# mount.net
KiCad netlist of a schematic drawn in EAGLE
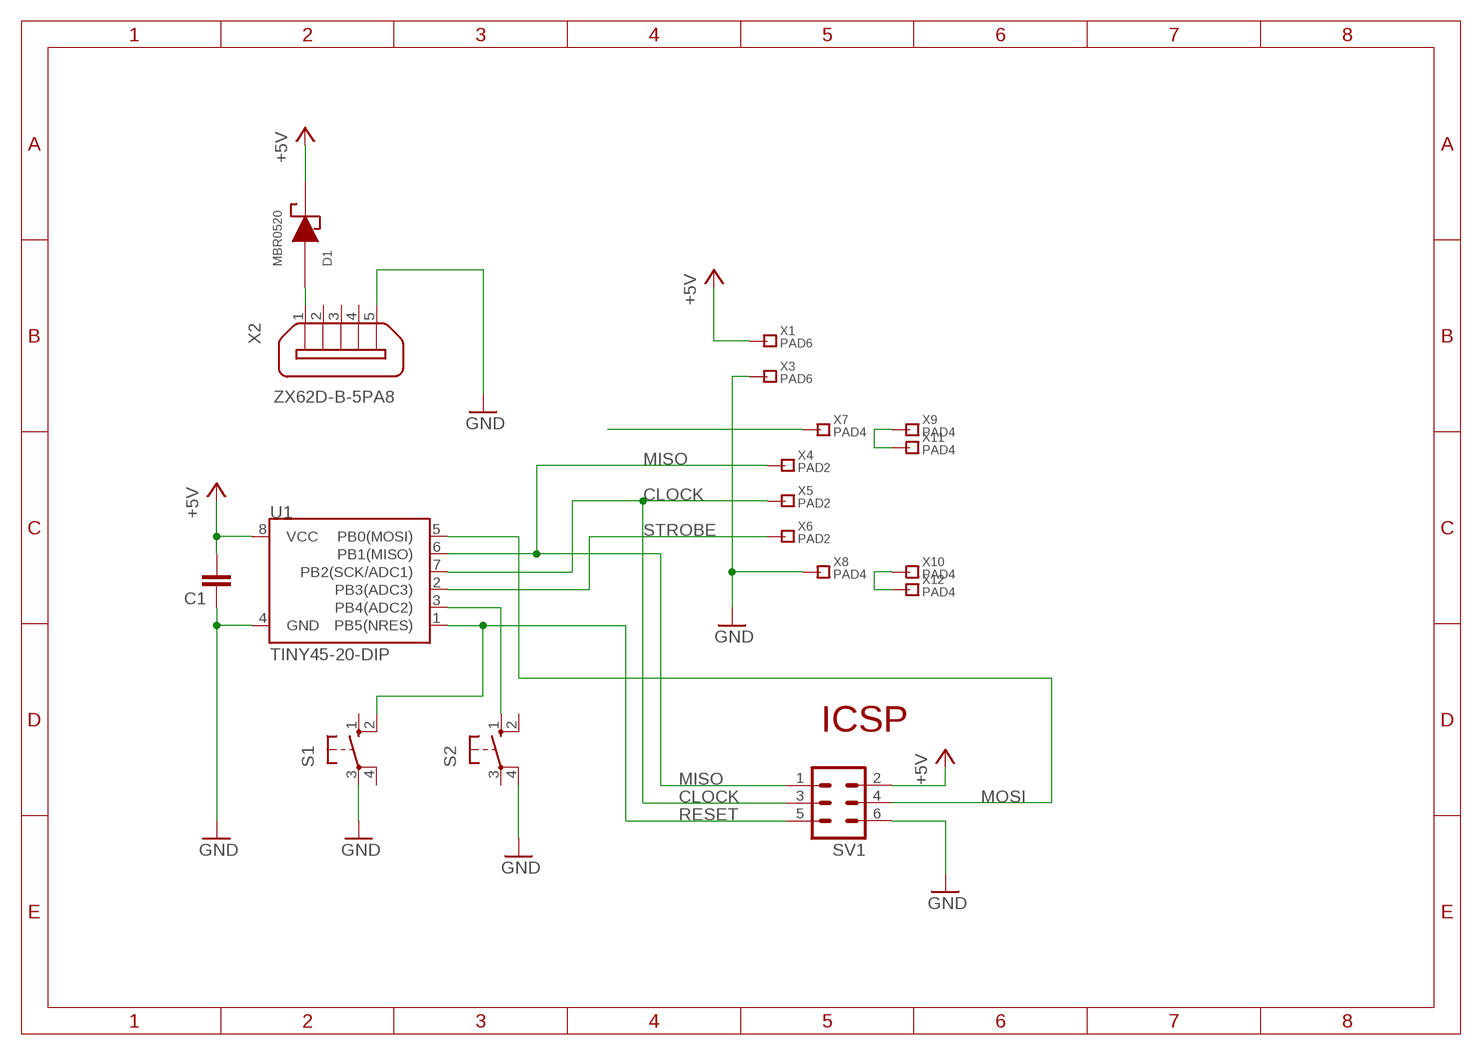
[diagram p0: schematic, sheet 1]

(export (version "E")
  (design (tool "Eeschema 10.0.6"))
  (components
    (comp (ref "C1")
      (value "C-EUC0805")
      (footprint "eagle-import:C0805")
      (libsource (lib "eagle-import") (part "C-EUC0805"))
    )
    (comp (ref "D1")
      (value "MBR0520")
      (footprint "eagle-import:SOD-123")
      (libsource (lib "eagle-import") (part "MBR0520"))
    )
    (comp (ref "S1")
      (value "10-XX")
      (footprint "eagle-import:B3F-10XX")
      (fields (field (name "MPN") "B3F-1000"))
      (libsource (lib "eagle-import") (part "10-XX"))
    )
    (comp (ref "S2")
      (value "10-XX")
      (footprint "eagle-import:B3F-10XX")
      (fields (field (name "MPN") "B3F-1000"))
      (libsource (lib "eagle-import") (part "10-XX"))
    )
    (comp (ref "SV1")
      (value "MA03-2")
      (footprint "eagle-import:MA03-2")
      (libsource (lib "eagle-import") (part "MA03-2"))
    )
    (comp (ref "U1")
      (value "TINY45-20-DIP")
      (footprint "eagle-import:DIP08_MCU")
      (libsource (lib "eagle-import") (part "ATTINY45TINY45-20-DIP"))
    )
    (comp (ref "X1")
      (value "PAD6")
      (footprint "eagle-import:SMDPAD")
      (libsource (lib "eagle-import") (part "PAD6"))
    )
    (comp (ref "X2")
      (value "ZX62D-B-5PA8")
      (footprint "eagle-import:ZX62D-B-5PA8")
      (fields (field (name "MF") "Hirose"))
      (libsource (lib "eagle-import") (part "ZX62D-B-5PA8"))
    )
    (comp (ref "X3")
      (value "PAD6")
      (footprint "eagle-import:SMDPAD")
      (libsource (lib "eagle-import") (part "PAD6"))
    )
    (comp (ref "X4")
      (value "PAD2")
      (footprint "eagle-import:SMDPAD_S")
      (libsource (lib "eagle-import") (part "PAD2"))
    )
    (comp (ref "X5")
      (value "PAD2")
      (footprint "eagle-import:SMDPAD_S")
      (libsource (lib "eagle-import") (part "PAD2"))
    )
    (comp (ref "X6")
      (value "PAD2")
      (footprint "eagle-import:SMDPAD_S")
      (libsource (lib "eagle-import") (part "PAD2"))
    )
    (comp (ref "X7")
      (value "PAD4")
      (footprint "eagle-import:SMDPAD_M")
      (libsource (lib "eagle-import") (part "PAD4"))
    )
    (comp (ref "X8")
      (value "PAD4")
      (footprint "eagle-import:SMDPAD_M")
      (libsource (lib "eagle-import") (part "PAD4"))
    )
    (comp (ref "X9")
      (value "PAD4")
      (footprint "eagle-import:SMDPAD_M")
      (libsource (lib "eagle-import") (part "PAD4"))
    )
    (comp (ref "X10")
      (value "PAD4")
      (footprint "eagle-import:SMDPAD_M")
      (libsource (lib "eagle-import") (part "PAD4"))
    )
    (comp (ref "X11")
      (value "PAD4")
      (footprint "eagle-import:SMDPAD_M")
      (libsource (lib "eagle-import") (part "PAD4"))
    )
    (comp (ref "X12")
      (value "PAD4")
      (footprint "eagle-import:SMDPAD_M")
      (libsource (lib "eagle-import") (part "PAD4"))
    )
  )
  (nets
    (net (code "1") (name "+5V") (class "Default")
      (node (ref "C1") (pin "2") (pinfunction "2_2") (pintype "passive"))
      (node (ref "D1") (pin "1") (pinfunction "CA_1") (pintype "passive"))
      (node (ref "SV1") (pin "2") (pinfunction "2_2") (pintype "passive"))
      (node (ref "U1") (pin "8") (pinfunction "VCC_8") (pintype "bidirectional"))
      (node (ref "X1") (pin "P$1") (pinfunction "P$1_P$1") (pintype "bidirectional"))
    )
    (net (code "2") (name "/CLOCK") (class "Default")
      (node (ref "SV1") (pin "3") (pinfunction "3_3") (pintype "passive"))
      (node (ref "U1") (pin "7") (pinfunction "PB2(SCK/ADC1)_7") (pintype "bidirectional"))
      (node (ref "X5") (pin "P$1") (pinfunction "P$1_P$1") (pintype "bidirectional"))
    )
    (net (code "3") (name "/MISO") (class "Default")
      (node (ref "SV1") (pin "1") (pinfunction "1_1") (pintype "passive"))
      (node (ref "U1") (pin "6") (pinfunction "PB1(MISO)_6") (pintype "bidirectional"))
      (node (ref "X4") (pin "P$1") (pinfunction "P$1_P$1") (pintype "bidirectional"))
    )
    (net (code "4") (name "/MOSI") (class "Default")
      (node (ref "SV1") (pin "4") (pinfunction "4_4") (pintype "passive"))
      (node (ref "U1") (pin "5") (pinfunction "PB0(MOSI)_5") (pintype "bidirectional"))
    )
    (net (code "5") (name "/RESET") (class "Default")
      (node (ref "S1") (pin "2") (pinfunction "S1_2") (pintype "passive"))
      (node (ref "SV1") (pin "5") (pinfunction "5_5") (pintype "passive"))
      (node (ref "U1") (pin "1") (pinfunction "PB5(NRES)_1") (pintype "bidirectional"))
    )
    (net (code "6") (name "/STROBE") (class "Default")
      (node (ref "U1") (pin "2") (pinfunction "PB3(ADC3)_2") (pintype "bidirectional"))
      (node (ref "X6") (pin "P$1") (pinfunction "P$1_P$1") (pintype "bidirectional"))
    )
    (net (code "7") (name "GND") (class "Default")
      (node (ref "C1") (pin "1") (pinfunction "1_1") (pintype "passive"))
      (node (ref "S1") (pin "3") (pinfunction "P_3") (pintype "passive"))
      (node (ref "S2") (pin "4") (pinfunction "P1_4") (pintype "passive"))
      (node (ref "SV1") (pin "6") (pinfunction "6_6") (pintype "passive"))
      (node (ref "U1") (pin "4") (pinfunction "GND_4") (pintype "bidirectional"))
      (node (ref "X2") (pin "5") (pinfunction "5_5") (pintype "passive"))
      (node (ref "X3") (pin "P$1") (pinfunction "P$1_P$1") (pintype "bidirectional"))
      (node (ref "X8") (pin "P$1") (pinfunction "P$1_P$1") (pintype "bidirectional"))
    )
    (net (code "8") (name "Net-(D1-AN)") (class "Default")
      (node (ref "D1") (pin "2") (pinfunction "AN_2") (pintype "passive"))
      (node (ref "X2") (pin "1") (pinfunction "1_1") (pintype "passive"))
    )
    (net (code "9") (name "Net-(S2-S)") (class "Default")
      (node (ref "S2") (pin "1") (pinfunction "S_1") (pintype "passive"))
      (node (ref "U1") (pin "3") (pinfunction "PB4(ADC2)_3") (pintype "bidirectional"))
    )
    (net (code "10") (name "Net-(X10-PadP$1)") (class "Default")
      (node (ref "X10") (pin "P$1") (pinfunction "P$1_P$1") (pintype "bidirectional"))
      (node (ref "X12") (pin "P$1") (pinfunction "P$1_P$1") (pintype "bidirectional"))
    )
    (net (code "11") (name "Net-(X11-PadP$1)") (class "Default")
      (node (ref "X11") (pin "P$1") (pinfunction "P$1_P$1") (pintype "bidirectional"))
      (node (ref "X9") (pin "P$1") (pinfunction "P$1_P$1") (pintype "bidirectional"))
    )
    (net (code "12") (name "unconnected-(S1-P1-Pad4)") (class "Default")
      (node (ref "S1") (pin "4") (pinfunction "P1_4") (pintype "passive"))
    )
    (net (code "13") (name "unconnected-(S1-S-Pad1)") (class "Default")
      (node (ref "S1") (pin "1") (pinfunction "S_1") (pintype "passive"))
    )
    (net (code "14") (name "unconnected-(S2-P-Pad3)") (class "Default")
      (node (ref "S2") (pin "3") (pinfunction "P_3") (pintype "passive"))
    )
    (net (code "15") (name "unconnected-(S2-S1-Pad2)") (class "Default")
      (node (ref "S2") (pin "2") (pinfunction "S1_2") (pintype "passive"))
    )
    (net (code "16") (name "unconnected-(X2-Pad2)") (class "Default")
      (node (ref "X2") (pin "2") (pinfunction "2_2") (pintype "passive"))
    )
    (net (code "17") (name "unconnected-(X2-Pad3)") (class "Default")
      (node (ref "X2") (pin "3") (pinfunction "3_3") (pintype "passive"))
    )
    (net (code "18") (name "unconnected-(X2-Pad4)") (class "Default")
      (node (ref "X2") (pin "4") (pinfunction "4_4") (pintype "passive"))
    )
    (net (code "19") (name "unconnected-(X7-PadP$1)") (class "Default")
      (node (ref "X7") (pin "P$1") (pinfunction "P$1_P$1") (pintype "bidirectional"))
    )
  )
)
